# schematic.net
KiCad netlist of a schematic drawn in EasyEDA
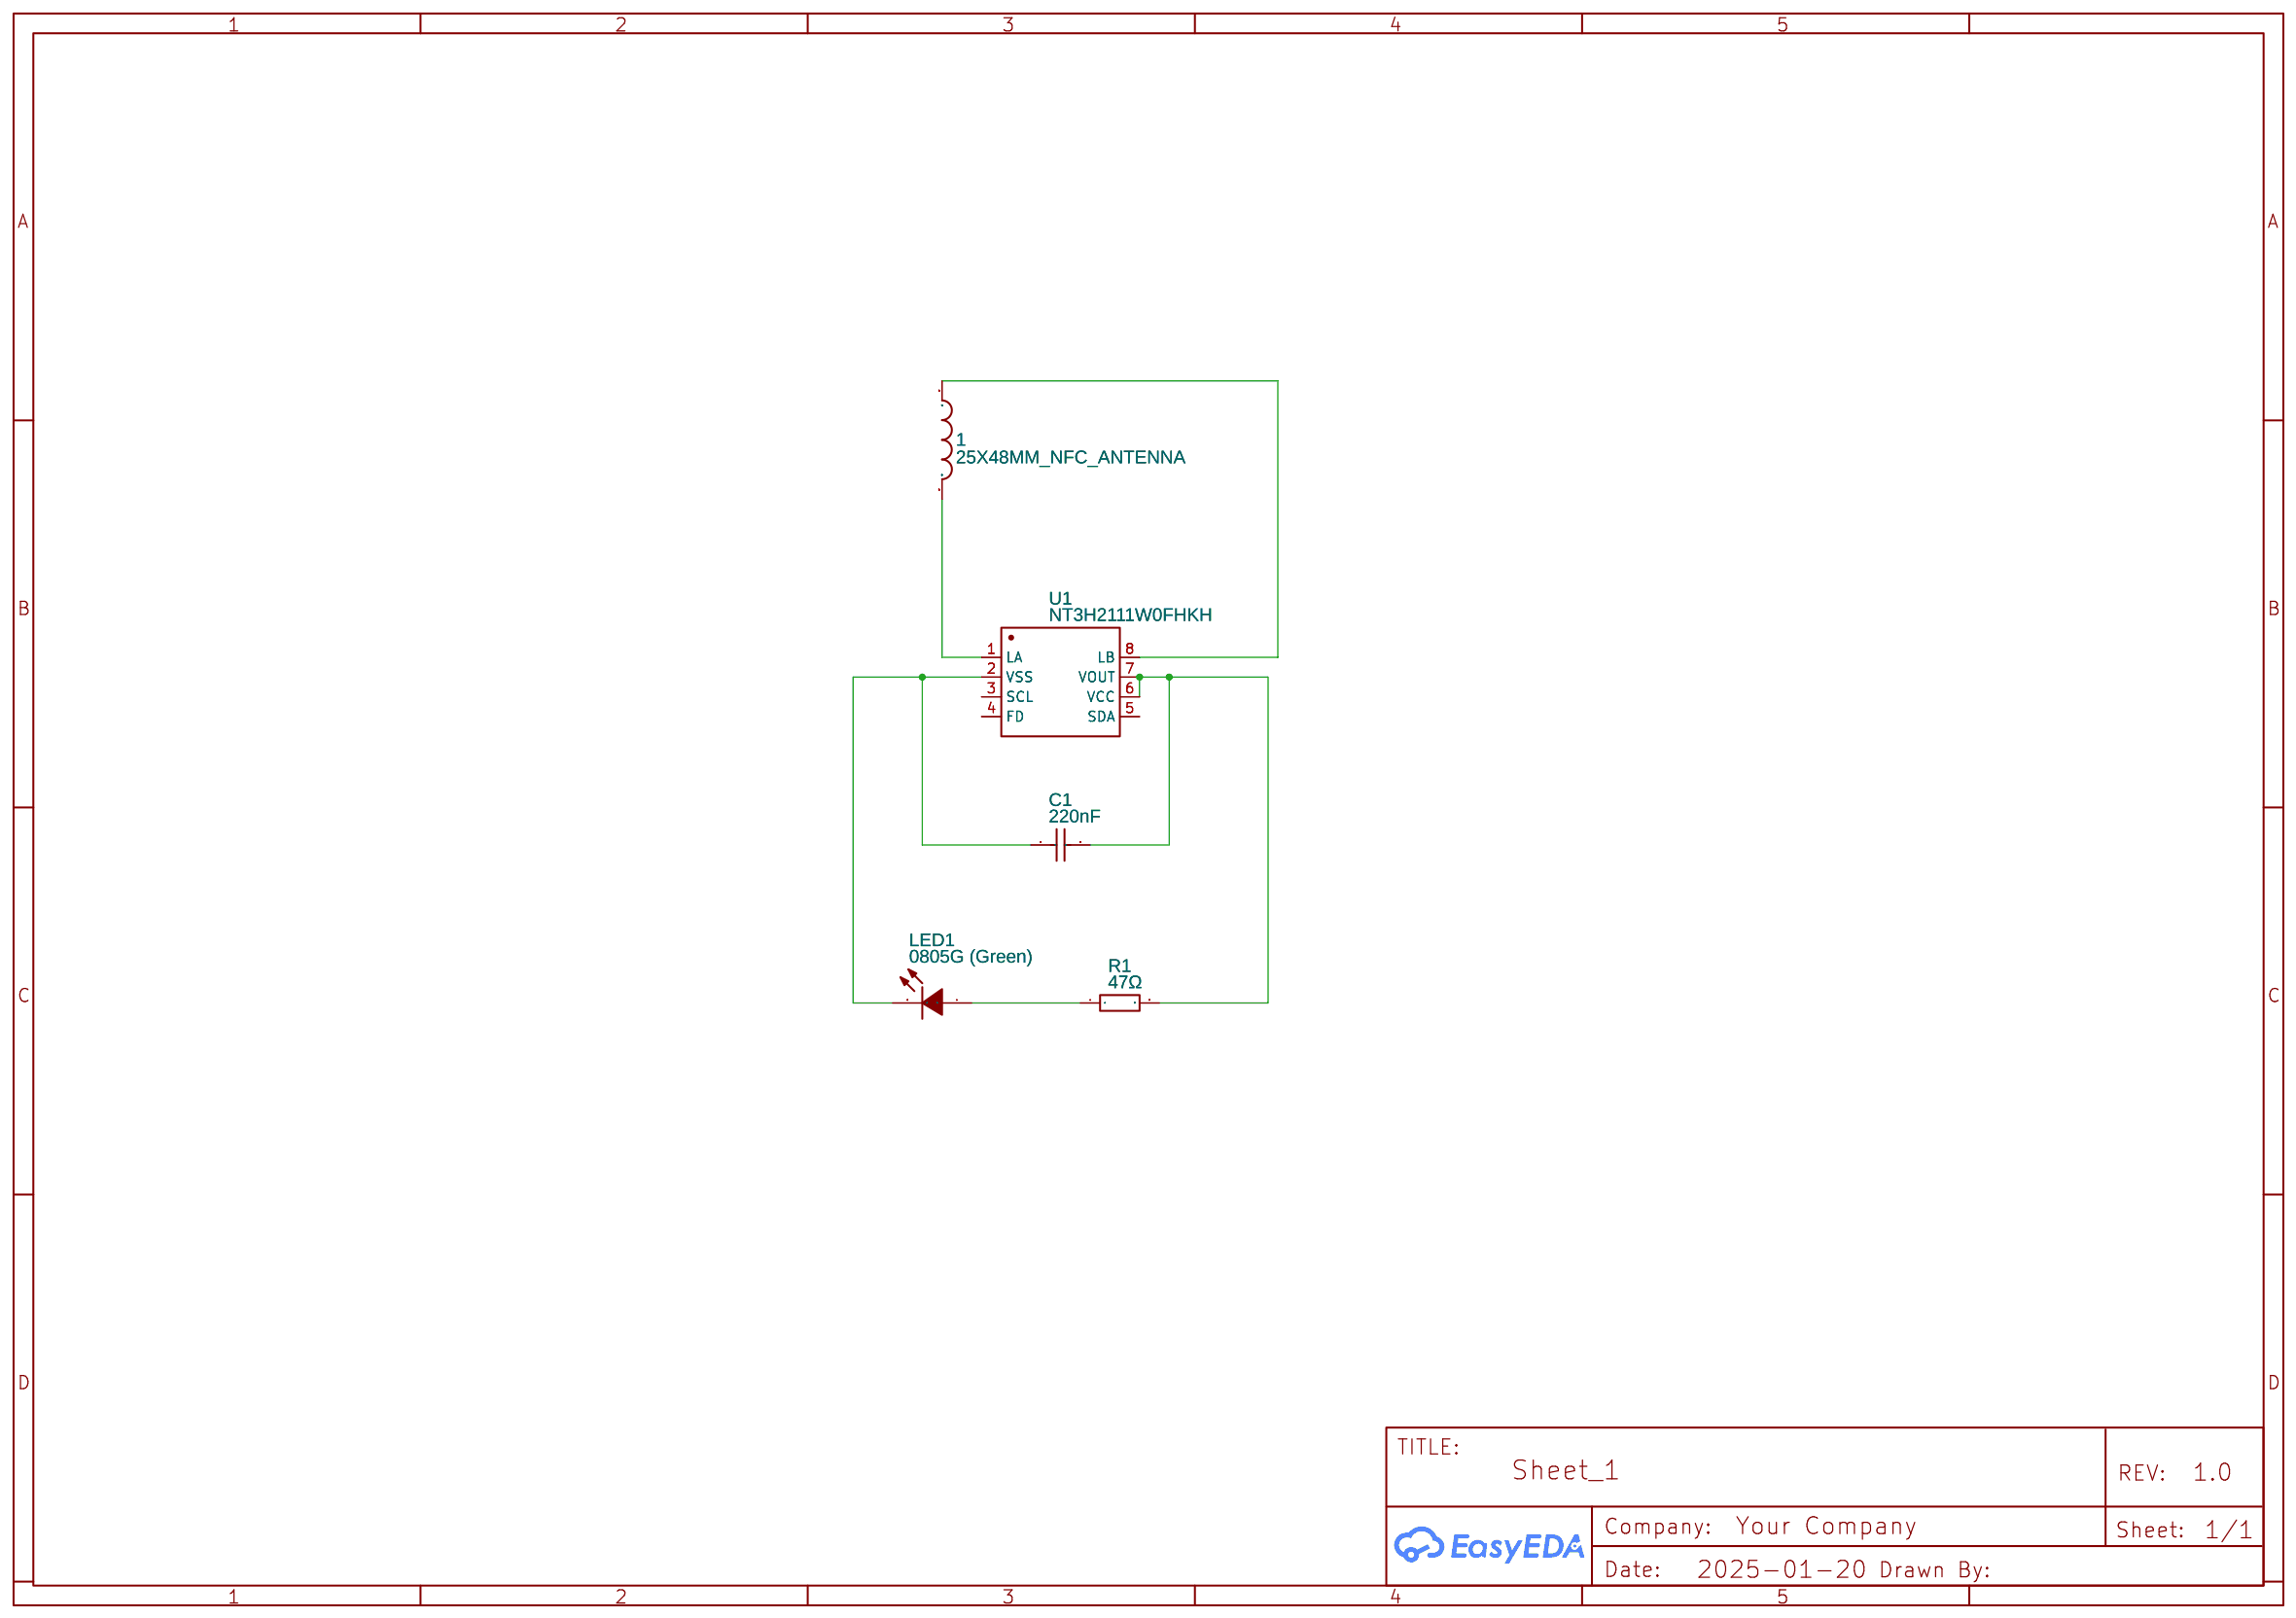
[diagram p0: schematic sheet]

(export (version "E")
  (design (tool "Eeschema 10.0.6"))
  (components
    (comp (ref "1") (value "25X48MM_NFC_ANTENNA") (libsource (lib "") (part "25X48MM_NFC_ANTENNA")))
    (comp (ref "C1")
      (value "220nF")
      (fields
        (field (name "Manufacturer Part") "CL10B224KA8NNNC")
        (field (name "Manufacturer") "SAMSUNG(三星)")
      )
      (libsource (lib "") (part "CL10B224KA8NNNC"))
    )
    (comp (ref "LED1")
      (value "0805G (Green)")
      (fields (field (name "Manufacturer Part") "KT-0805G") (field (name "Manufacturer") "KENTO"))
      (libsource (lib "") (part "0805G (Green)"))
    )
    (comp (ref "R1")
      (value "47Ω")
      (fields
        (field (name "Manufacturer Part") "0603WAF470JT5E")
        (field (name "Manufacturer") "UNI-ROYAL(厚声)")
      )
      (libsource (lib "") (part "0603WAF470JT5E"))
    )
    (comp (ref "U1")
      (value "NT3H2111W0FHKH")
      (fields (field (name "Manufacturer") "NXP(恩智浦)"))
      (libsource (lib "") (part "NT3H2111W0FHKH"))
    )
  )
  (nets
    (net (code "1") (name "Net-(LED1-A)") (class "Default")
      (node (ref "LED1") (pin "1") (pinfunction "A_1") (pintype "unspecified"))
      (node (ref "R1") (pin "1") (pinfunction "1_1") (pintype "input"))
    )
    (net (code "2") (name "Net-(LED1-K)") (class "Default")
      (node (ref "C1") (pin "1") (pinfunction "1_1") (pintype "input"))
      (node (ref "LED1") (pin "2") (pinfunction "K_2") (pintype "unspecified"))
      (node (ref "U1") (pin "2") (pinfunction "VSS_2") (pintype "unspecified"))
    )
    (net (code "3") (name "Net-(U1-LA)") (class "Default")
      (node (ref "1") (pin "P$2") (pinfunction "P$2_P$2") (pintype "bidirectional"))
      (node (ref "U1") (pin "1") (pinfunction "LA_1") (pintype "unspecified"))
    )
    (net (code "4") (name "Net-(U1-LB)") (class "Default")
      (node (ref "1") (pin "P$1") (pinfunction "P$1_P$1") (pintype "bidirectional"))
      (node (ref "U1") (pin "8") (pinfunction "LB_8") (pintype "unspecified"))
    )
    (net (code "5") (name "Net-(U1-VCC)") (class "Default")
      (node (ref "C1") (pin "2") (pinfunction "2_2") (pintype "input"))
      (node (ref "R1") (pin "2") (pinfunction "2_2") (pintype "input"))
      (node (ref "U1") (pin "6") (pinfunction "VCC_6") (pintype "unspecified"))
      (node (ref "U1") (pin "7") (pinfunction "VOUT_7") (pintype "unspecified"))
    )
    (net (code "6") (name "unconnected-(U1-FD-Pad4)") (class "Default")
      (node (ref "U1") (pin "4") (pinfunction "FD_4") (pintype "unspecified"))
    )
    (net (code "7") (name "unconnected-(U1-SCL-Pad3)") (class "Default")
      (node (ref "U1") (pin "3") (pinfunction "SCL_3") (pintype "unspecified"))
    )
    (net (code "8") (name "unconnected-(U1-SDA-Pad5)") (class "Default")
      (node (ref "U1") (pin "5") (pinfunction "SDA_5") (pintype "unspecified"))
    )
  )
)
